# ch559.net
KiCad netlist of a schematic drawn in Altium Designer
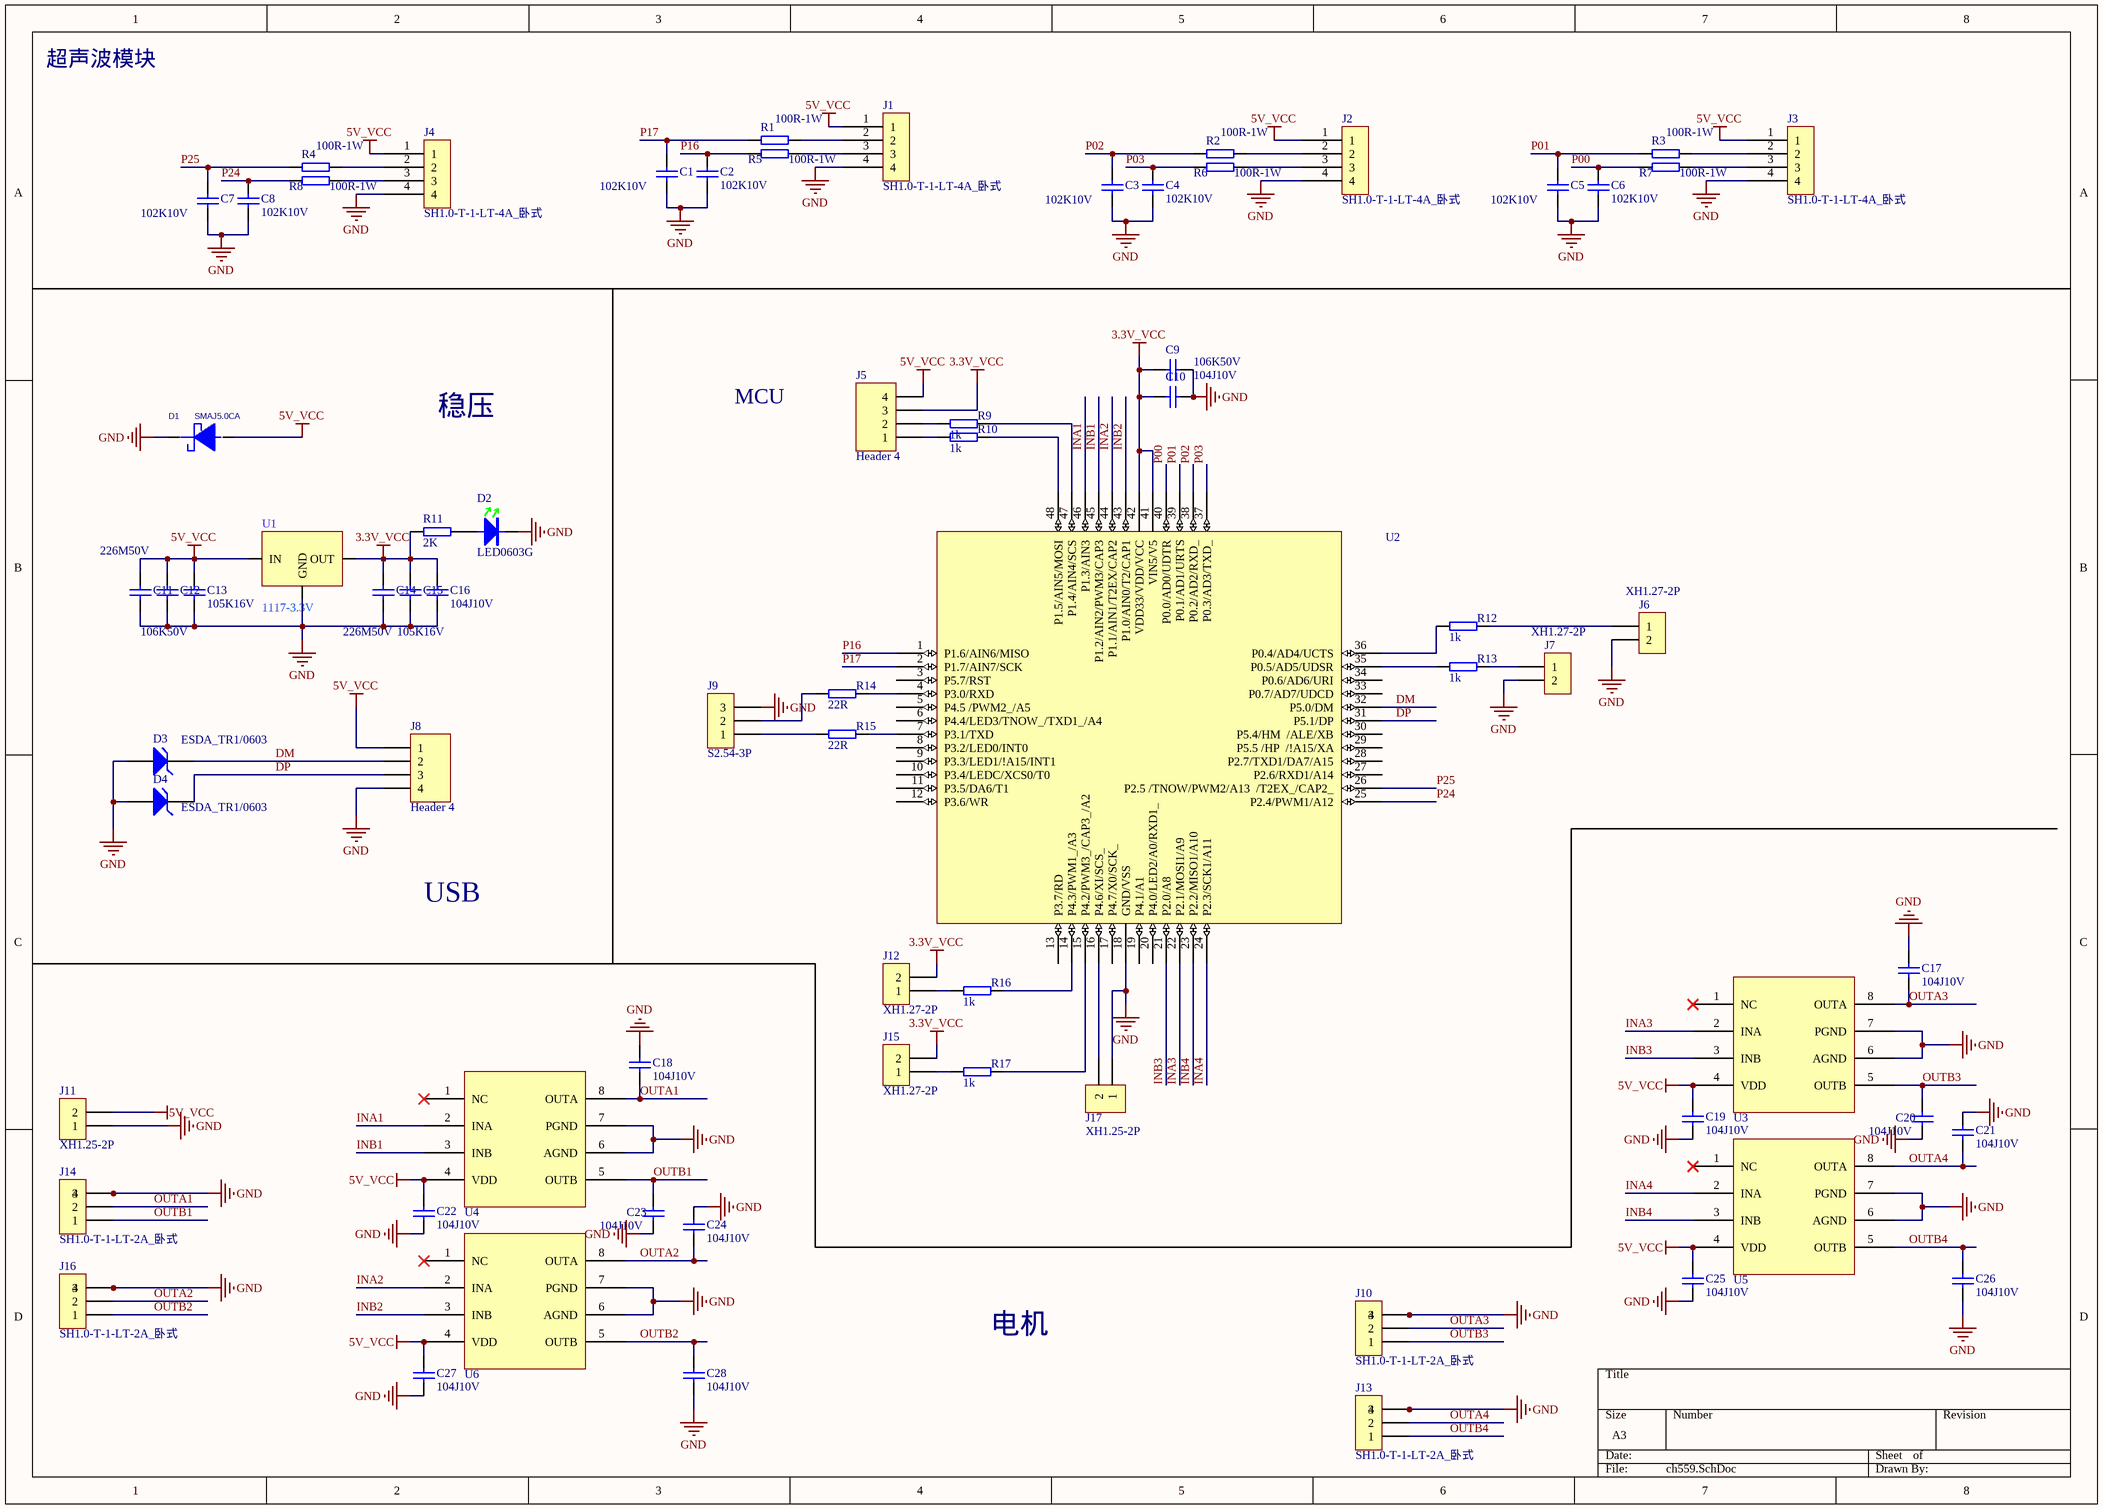
[diagram p0: ch559.SchDoc]

(export (version "E")
  (design (tool "Eeschema 10.0.6"))
  (components
    (comp (ref "C1")
      (value "102K10V")
      (footprint "C0603")
      (description "贴片电容-陶瓷")
      (libsource (lib "Capacitor") (part "C0603X7R-102K10V"))
    )
    (comp (ref "C2")
      (value "102K10V")
      (footprint "C0603")
      (description "贴片电容-陶瓷")
      (libsource (lib "Capacitor") (part "C0603X7R-102K10V"))
    )
    (comp (ref "C3")
      (value "102K10V")
      (footprint "C0603")
      (description "贴片电容-陶瓷")
      (libsource (lib "Capacitor") (part "C0603X7R-102K10V"))
    )
    (comp (ref "C4")
      (value "102K10V")
      (footprint "C0603")
      (description "贴片电容-陶瓷")
      (libsource (lib "Capacitor") (part "C0603X7R-102K10V"))
    )
    (comp (ref "C5")
      (value "102K10V")
      (footprint "C0603")
      (description "贴片电容-陶瓷")
      (libsource (lib "Capacitor") (part "C0603X7R-102K10V"))
    )
    (comp (ref "C6")
      (value "102K10V")
      (footprint "C0603")
      (description "贴片电容-陶瓷")
      (libsource (lib "Capacitor") (part "C0603X7R-102K10V"))
    )
    (comp (ref "C7")
      (value "102K10V")
      (footprint "C0603")
      (description "贴片电容-陶瓷")
      (libsource (lib "Capacitor") (part "C0603X7R-102K10V"))
    )
    (comp (ref "C8")
      (value "102K10V")
      (footprint "C0603")
      (description "贴片电容-陶瓷")
      (libsource (lib "Capacitor") (part "C0603X7R-102K10V"))
    )
    (comp (ref "C9")
      (value "106K50V")
      (footprint "C0603")
      (description "贴片电容-陶瓷")
      (libsource (lib "AIWAC-bolsterV01") (part "C0603X7R-106K50V"))
    )
    (comp (ref "C10")
      (value "104J10V")
      (footprint "C0402")
      (description "贴片电容-陶瓷")
      (libsource (lib "AIWAC-bolsterV01") (part "C0402X7R-104J10V"))
    )
    (comp (ref "C11")
      (value "226M50V")
      (footprint "C0805")
      (description "贴片电容-陶瓷")
      (libsource (lib "AIWAC-bolsterV01") (part "C0805Y5V-226M50V"))
    )
    (comp (ref "C12")
      (value "106K50V")
      (footprint "C0603")
      (description "贴片电容-陶瓷")
      (libsource (lib "AIWAC-bolsterV01") (part "C0603X7R-106K50V"))
    )
    (comp (ref "C13")
      (value "105K16V")
      (footprint "C0603")
      (description "贴片电容-陶瓷")
      (libsource (lib "AIWAC-bolsterV01") (part "C0603X7R-105K16V"))
    )
    (comp (ref "C14")
      (value "226M50V")
      (footprint "C0805")
      (description "贴片电容-陶瓷")
      (libsource (lib "AIWAC-bolsterV01") (part "C0805Y5V-226M50V"))
    )
    (comp (ref "C15")
      (value "105K16V")
      (footprint "C0603")
      (description "贴片电容-陶瓷")
      (libsource (lib "AIWAC-bolsterV01") (part "C0603X7R-105K16V"))
    )
    (comp (ref "C16")
      (value "104J10V")
      (footprint "C0402")
      (description "贴片电容-陶瓷")
      (libsource (lib "AIWAC-bolsterV01") (part "C0402X7R-104J10V"))
    )
    (comp (ref "C17")
      (value "104J10V")
      (footprint "C0402")
      (description "贴片电容-陶瓷")
      (libsource (lib "AIWAC-bolsterV01") (part "C0402X7R-104J10V"))
    )
    (comp (ref "C18")
      (value "104J10V")
      (footprint "C0402")
      (description "贴片电容-陶瓷")
      (libsource (lib "AIWAC-bolsterV01") (part "C0402X7R-104J10V"))
    )
    (comp (ref "C19")
      (value "104J10V")
      (footprint "C0402")
      (description "贴片电容-陶瓷")
      (libsource (lib "AIWAC-bolsterV01") (part "C0402X7R-104J10V"))
    )
    (comp (ref "C20")
      (value "104J10V")
      (footprint "C0402")
      (description "贴片电容-陶瓷")
      (libsource (lib "AIWAC-bolsterV01") (part "C0402X7R-104J10V"))
    )
    (comp (ref "C21")
      (value "104J10V")
      (footprint "C0402")
      (description "贴片电容-陶瓷")
      (libsource (lib "AIWAC-bolsterV01") (part "C0402X7R-104J10V"))
    )
    (comp (ref "C22")
      (value "104J10V")
      (footprint "C0402")
      (description "贴片电容-陶瓷")
      (libsource (lib "AIWAC-bolsterV01") (part "C0402X7R-104J10V"))
    )
    (comp (ref "C23")
      (value "104J10V")
      (footprint "C0402")
      (description "贴片电容-陶瓷")
      (libsource (lib "AIWAC-bolsterV01") (part "C0402X7R-104J10V"))
    )
    (comp (ref "C24")
      (value "104J10V")
      (footprint "C0402")
      (description "贴片电容-陶瓷")
      (libsource (lib "AIWAC-bolsterV01") (part "C0402X7R-104J10V"))
    )
    (comp (ref "C25")
      (value "104J10V")
      (footprint "C0402")
      (description "贴片电容-陶瓷")
      (libsource (lib "AIWAC-bolsterV01") (part "C0402X7R-104J10V"))
    )
    (comp (ref "C26")
      (value "104J10V")
      (footprint "C0402")
      (description "贴片电容-陶瓷")
      (libsource (lib "AIWAC-bolsterV01") (part "C0402X7R-104J10V"))
    )
    (comp (ref "C27")
      (value "104J10V")
      (footprint "C0402")
      (description "贴片电容-陶瓷")
      (libsource (lib "AIWAC-bolsterV01") (part "C0402X7R-104J10V"))
    )
    (comp (ref "C28")
      (value "104J10V")
      (footprint "C0402")
      (description "贴片电容-陶瓷")
      (libsource (lib "AIWAC-bolsterV01") (part "C0402X7R-104J10V"))
    )
    (comp (ref "D1") (value "SMAJ5.0CA") (footprint "DO-214") (libsource (lib "ISO-V3") (part "SMAJ5.0CA")))
    (comp (ref "D2")
      (value "LED0603G")
      (footprint "D-LED0603G")
      (description "贴片二极管-LED")
      (libsource (lib "AIWAC-bolsterV01") (part "DLED-0603-G"))
    )
    (comp (ref "D3")
      (value "ESDA_TR1/0603")
      (footprint "HS_0603D")
      (description "Zener Diode")
      (fields (field (name "PUBLISHER") "*"))
      (libsource (lib "HSC32K1(QFN56)_BlueTooth_V2.0_20171108 - 副本") (part "D Zener"))
    )
    (comp (ref "D4")
      (value "ESDA_TR1/0603")
      (footprint "HS_0603D")
      (description "Zener Diode")
      (fields (field (name "PUBLISHER") "*"))
      (libsource (lib "HSC32K1(QFN56)_BlueTooth_V2.0_20171108 - 副本") (part "D Zener"))
    )
    (comp (ref "J1")
      (value "SH1.0-T-1-LT-4A_卧式")
      (footprint "XH2.54-4P")
      (libsource (lib "Schlib1") (part "SH1.0-T-1-LT-4A_卧式"))
    )
    (comp (ref "J2")
      (value "SH1.0-T-1-LT-4A_卧式")
      (footprint "XH2.54-4P")
      (libsource (lib "Schlib1") (part "SH1.0-T-1-LT-4A_卧式"))
    )
    (comp (ref "J3")
      (value "SH1.0-T-1-LT-4A_卧式")
      (footprint "XH2.54-4P")
      (libsource (lib "Schlib1") (part "SH1.0-T-1-LT-4A_卧式"))
    )
    (comp (ref "J4")
      (value "SH1.0-T-1-LT-4A_卧式")
      (footprint "XH2.54-4P")
      (libsource (lib "Schlib1") (part "SH1.0-T-1-LT-4A_卧式"))
    )
    (comp (ref "J5")
      (value "Header 4")
      (footprint "J-SH1.27 -4")
      (description "Header, 4-Pin")
      (fields (field (name "PUBLISHER") "Altium Limited"))
      (libsource (lib "USB_COM_V1.0") (part "Header 4"))
    )
    (comp (ref "J6")
      (value "XH1.27-2P")
      (footprint "J-SH1.27-2")
      (description "接插件-1.27")
      (libsource (lib "USB_COM_V1.0") (part "J-XH1.27-2P"))
    )
    (comp (ref "J7")
      (value "XH1.27-2P")
      (footprint "J-SH1.27-2")
      (description "接插件-1.27")
      (libsource (lib "USB_COM_V1.0") (part "J-XH1.27-2P"))
    )
    (comp (ref "J8")
      (value "Header 4")
      (footprint "XH2.54-4P")
      (description "Header, 4-Pin")
      (fields (field (name "PUBLISHER") "Altium Limited"))
      (libsource (lib "Miscellaneous Connectors") (part "Header 4"))
    )
    (comp (ref "J9")
      (value "S2.54-3P")
      (footprint "S2.54-3P")
      (description "单排排针-直针")
      (libsource (lib "PCB_Project") (part "J-S2.54-3P"))
    )
    (comp (ref "J10")
      (value "SH1.0-T-1-LT-2A_卧式")
      (footprint "J-SH2.0-T-1-LT-2A_立式")
      (libsource (lib "Connector") (part "SH1.0-T-1-LT-2A_卧式"))
    )
    (comp (ref "J11")
      (value "XH1.25-2P")
      (footprint "XH2.54-2p")
      (description "接插件-2.54")
      (libsource (lib "USB_COM_V1.0") (part "J-XH2.54-2P_1"))
    )
    (comp (ref "J12")
      (value "XH1.27-2P")
      (footprint "J-SH1.27-2")
      (description "接插件-1.27")
      (libsource (lib "") (part "J-XH1.27-2P_1"))
    )
    (comp (ref "J13")
      (value "SH1.0-T-1-LT-2A_卧式")
      (footprint "J-SH2.0-T-1-LT-2A_立式")
      (libsource (lib "Connector") (part "SH1.0-T-1-LT-2A_卧式"))
    )
    (comp (ref "J14")
      (value "SH1.0-T-1-LT-2A_卧式")
      (footprint "J-SH2.0-T-1-LT-2A_立式")
      (libsource (lib "Connector") (part "SH1.0-T-1-LT-2A_卧式"))
    )
    (comp (ref "J15")
      (value "XH1.27-2P")
      (footprint "J-SH1.27-2")
      (description "接插件-1.27")
      (libsource (lib "") (part "J-XH1.27-2P_1"))
    )
    (comp (ref "J16")
      (value "SH1.0-T-1-LT-2A_卧式")
      (footprint "J-SH2.0-T-1-LT-2A_立式")
      (libsource (lib "Connector") (part "SH1.0-T-1-LT-2A_卧式"))
    )
    (comp (ref "J17")
      (value "XH1.25-2P")
      (footprint "S1.25-2P")
      (description "接插件-2.54")
      (libsource (lib "AIWAC-bolsterV01") (part "J-XH2.54-2P"))
    )
    (comp (ref "R1")
      (value "100R-1W")
      (footprint "R0603")
      (description "插件电阻-碳膜")
      (libsource (lib "Resistor") (part "R1-100R"))
    )
    (comp (ref "R2")
      (value "100R-1W")
      (footprint "R0603")
      (description "插件电阻-碳膜")
      (libsource (lib "Resistor") (part "R1-100R"))
    )
    (comp (ref "R3")
      (value "100R-1W")
      (footprint "R0603")
      (description "插件电阻-碳膜")
      (libsource (lib "Resistor") (part "R1-100R"))
    )
    (comp (ref "R4")
      (value "100R-1W")
      (footprint "R0603")
      (description "插件电阻-碳膜")
      (libsource (lib "Resistor") (part "R1-100R"))
    )
    (comp (ref "R5")
      (value "100R-1W")
      (footprint "R0603")
      (description "插件电阻-碳膜")
      (libsource (lib "Resistor") (part "R1-100R"))
    )
    (comp (ref "R6")
      (value "100R-1W")
      (footprint "R0603")
      (description "插件电阻-碳膜")
      (libsource (lib "Resistor") (part "R1-100R"))
    )
    (comp (ref "R7")
      (value "100R-1W")
      (footprint "R0603")
      (description "插件电阻-碳膜")
      (libsource (lib "Resistor") (part "R1-100R"))
    )
    (comp (ref "R8")
      (value "100R-1W")
      (footprint "R0603")
      (description "插件电阻-碳膜")
      (libsource (lib "Resistor") (part "R1-100R"))
    )
    (comp (ref "R9")
      (value "1k")
      (footprint "R0603")
      (description "贴片电阻-通用")
      (libsource (lib "Resistor") (part "R0603-100RF"))
    )
    (comp (ref "R10")
      (value "1k")
      (footprint "R0603")
      (description "贴片电阻-通用")
      (libsource (lib "Resistor") (part "R0603-100RF"))
    )
    (comp (ref "R11")
      (value "2K")
      (footprint "R0603")
      (description "贴片电阻-通用")
      (libsource (lib "Resistor") (part "R0603-100RF"))
    )
    (comp (ref "R12")
      (value "1k")
      (footprint "R0603")
      (description "贴片电阻-通用")
      (libsource (lib "Resistor") (part "R0603-100RF"))
    )
    (comp (ref "R13")
      (value "1k")
      (footprint "R0603")
      (description "贴片电阻-通用")
      (libsource (lib "Resistor") (part "R0603-100RF"))
    )
    (comp (ref "R14")
      (value "22R")
      (footprint "R0603")
      (description "贴片电阻-通用")
      (libsource (lib "Resistor") (part "R0603-100RF"))
    )
    (comp (ref "R15")
      (value "22R")
      (footprint "R0603")
      (description "贴片电阻-通用")
      (libsource (lib "Resistor") (part "R0603-100RF"))
    )
    (comp (ref "R16")
      (value "1k")
      (footprint "R0603")
      (description "贴片电阻-通用")
      (libsource (lib "Resistor") (part "R0603-100RF"))
    )
    (comp (ref "R17")
      (value "1k")
      (footprint "R0603")
      (description "贴片电阻-通用")
      (libsource (lib "Resistor") (part "R0603-100RF"))
    )
    (comp (ref "U1")
      (value "1117-3.3V")
      (footprint "SOT-223")
      (description "芯片 电源类")
      (libsource (lib "标准通用原理图库") (part "AP1117-33 SOT-223"))
    )
    (comp (ref "U2")
      (value "CH559L")
      (footprint "LQFP48")
      (description "单片机")
      (libsource (lib "PCB_Project") (part "CH559L"))
    )
    (comp (ref "U3")
      (value "PTC918")
      (footprint "SO-8")
      (description "马达驱动芯片")
      (libsource (lib "USB_COM_V1.0") (part "PTC918"))
    )
    (comp (ref "U4")
      (value "PTC918")
      (footprint "SO-8")
      (description "马达驱动芯片")
      (libsource (lib "USB_COM_V1.0") (part "PTC918"))
    )
    (comp (ref "U5")
      (value "PTC918")
      (footprint "SO-8")
      (description "马达驱动芯片")
      (libsource (lib "USB_COM_V1.0") (part "PTC918"))
    )
    (comp (ref "U6")
      (value "PTC918")
      (footprint "SO-8")
      (description "马达驱动芯片")
      (libsource (lib "USB_COM_V1.0") (part "PTC918"))
    )
  )
  (nets
    (net (code "1") (name "/DM") (class "Default")
      (node (ref "D3") (pin "2") (pinfunction "K_2") (pintype "passive"))
      (node (ref "J8") (pin "2") (pinfunction "2_2") (pintype "passive"))
      (node (ref "U2") (pin "32") (pinfunction "P5.0/DM_32") (pintype "bidirectional"))
    )
    (net (code "2") (name "/DP") (class "Default")
      (node (ref "D4") (pin "2") (pinfunction "K_2") (pintype "passive"))
      (node (ref "J8") (pin "3") (pinfunction "3_3") (pintype "passive"))
      (node (ref "U2") (pin "31") (pinfunction "P5.1/DP_31") (pintype "bidirectional"))
    )
    (net (code "3") (name "/INA1") (class "Default")
      (node (ref "U2") (pin "46") (pinfunction "P1.3/AIN3_46") (pintype "bidirectional"))
      (node (ref "U4") (pin "2") (pinfunction "INA_2") (pintype "passive"))
    )
    (net (code "4") (name "/INA2") (class "Default")
      (node (ref "U2") (pin "44") (pinfunction "P1.1/AIN1/T2EX/CAP2_44") (pintype "bidirectional"))
      (node (ref "U6") (pin "2") (pinfunction "INA_2") (pintype "passive"))
    )
    (net (code "5") (name "/INA3") (class "Default")
      (node (ref "U2") (pin "22") (pinfunction "P2.1/MOSI1/A9_22") (pintype "bidirectional"))
      (node (ref "U3") (pin "2") (pinfunction "INA_2") (pintype "passive"))
    )
    (net (code "6") (name "/INA4") (class "Default")
      (node (ref "U2") (pin "24") (pinfunction "P2.3/SCK1/A11_24") (pintype "bidirectional"))
      (node (ref "U5") (pin "2") (pinfunction "INA_2") (pintype "passive"))
    )
    (net (code "7") (name "/INB1") (class "Default")
      (node (ref "U2") (pin "45") (pinfunction "P1.2/AIN2/PWM3/CAP3_45") (pintype "bidirectional"))
      (node (ref "U4") (pin "3") (pinfunction "INB_3") (pintype "passive"))
    )
    (net (code "8") (name "/INB2") (class "Default")
      (node (ref "U2") (pin "43") (pinfunction "P1.0/AIN0/T2/CAP1_43") (pintype "bidirectional"))
      (node (ref "U6") (pin "3") (pinfunction "INB_3") (pintype "passive"))
    )
    (net (code "9") (name "/INB3") (class "Default")
      (node (ref "U2") (pin "21") (pinfunction "P2.0/A8_21") (pintype "bidirectional"))
      (node (ref "U3") (pin "3") (pinfunction "INB_3") (pintype "passive"))
    )
    (net (code "10") (name "/INB4") (class "Default")
      (node (ref "U2") (pin "23") (pinfunction "P2.2/MISO1/A10_23") (pintype "bidirectional"))
      (node (ref "U5") (pin "3") (pinfunction "INB_3") (pintype "passive"))
    )
    (net (code "11") (name "/OUTA1") (class "Default")
      (node (ref "C18") (pin "2") (pinfunction "2_2") (pintype "passive"))
      (node (ref "J14") (pin "2") (pinfunction "2_2") (pintype "passive"))
      (node (ref "U4") (pin "8") (pinfunction "OUTA_8") (pintype "passive"))
    )
    (net (code "12") (name "/OUTA2") (class "Default")
      (node (ref "C24") (pin "2") (pinfunction "2_2") (pintype "passive"))
      (node (ref "J16") (pin "2") (pinfunction "2_2") (pintype "passive"))
      (node (ref "U6") (pin "8") (pinfunction "OUTA_8") (pintype "passive"))
    )
    (net (code "13") (name "/OUTA3") (class "Default")
      (node (ref "C17") (pin "2") (pinfunction "2_2") (pintype "passive"))
      (node (ref "J10") (pin "2") (pinfunction "2_2") (pintype "passive"))
      (node (ref "U3") (pin "8") (pinfunction "OUTA_8") (pintype "passive"))
    )
    (net (code "14") (name "/OUTA4") (class "Default")
      (node (ref "C21") (pin "2") (pinfunction "2_2") (pintype "passive"))
      (node (ref "J13") (pin "2") (pinfunction "2_2") (pintype "passive"))
      (node (ref "U5") (pin "8") (pinfunction "OUTA_8") (pintype "passive"))
    )
    (net (code "15") (name "/OUTB1") (class "Default")
      (node (ref "C23") (pin "1") (pinfunction "1_1") (pintype "passive"))
      (node (ref "J14") (pin "1") (pinfunction "1_1") (pintype "passive"))
      (node (ref "U4") (pin "5") (pinfunction "OUTB_5") (pintype "passive"))
    )
    (net (code "16") (name "/OUTB2") (class "Default")
      (node (ref "C28") (pin "1") (pinfunction "1_1") (pintype "passive"))
      (node (ref "J16") (pin "1") (pinfunction "1_1") (pintype "passive"))
      (node (ref "U6") (pin "5") (pinfunction "OUTB_5") (pintype "passive"))
    )
    (net (code "17") (name "/OUTB3") (class "Default")
      (node (ref "C20") (pin "1") (pinfunction "1_1") (pintype "passive"))
      (node (ref "J10") (pin "1") (pinfunction "1_1") (pintype "passive"))
      (node (ref "U3") (pin "5") (pinfunction "OUTB_5") (pintype "passive"))
    )
    (net (code "18") (name "/OUTB4") (class "Default")
      (node (ref "C26") (pin "1") (pinfunction "1_1") (pintype "passive"))
      (node (ref "J13") (pin "1") (pinfunction "1_1") (pintype "passive"))
      (node (ref "U5") (pin "5") (pinfunction "OUTB_5") (pintype "passive"))
    )
    (net (code "19") (name "/P00") (class "Default")
      (node (ref "C6") (pin "1") (pinfunction "1_1") (pintype "passive"))
      (node (ref "R7") (pin "1") (pinfunction "1_1") (pintype "passive"))
      (node (ref "U2") (pin "40") (pinfunction "P0.0/AD0/UDTR_40") (pintype "bidirectional"))
    )
    (net (code "20") (name "/P01") (class "Default")
      (node (ref "C5") (pin "1") (pinfunction "1_1") (pintype "passive"))
      (node (ref "R3") (pin "1") (pinfunction "1_1") (pintype "passive"))
      (node (ref "U2") (pin "39") (pinfunction "P0.1/AD1/URTS_39") (pintype "bidirectional"))
    )
    (net (code "21") (name "/P02") (class "Default")
      (node (ref "C3") (pin "1") (pinfunction "1_1") (pintype "passive"))
      (node (ref "R2") (pin "1") (pinfunction "1_1") (pintype "passive"))
      (node (ref "U2") (pin "38") (pinfunction "P0.2/AD2/RXD__38") (pintype "bidirectional"))
    )
    (net (code "22") (name "/P03") (class "Default")
      (node (ref "C4") (pin "1") (pinfunction "1_1") (pintype "passive"))
      (node (ref "R6") (pin "1") (pinfunction "1_1") (pintype "passive"))
      (node (ref "U2") (pin "37") (pinfunction "P0.3/AD3/TXD__37") (pintype "bidirectional"))
    )
    (net (code "23") (name "/P16") (class "Default")
      (node (ref "C2") (pin "1") (pinfunction "1_1") (pintype "passive"))
      (node (ref "R5") (pin "1") (pinfunction "1_1") (pintype "passive"))
      (node (ref "U2") (pin "1") (pinfunction "P1.6/AIN6/MISO_1") (pintype "bidirectional"))
    )
    (net (code "24") (name "/P17") (class "Default")
      (node (ref "C1") (pin "1") (pinfunction "1_1") (pintype "passive"))
      (node (ref "R1") (pin "1") (pinfunction "1_1") (pintype "passive"))
      (node (ref "U2") (pin "2") (pinfunction "P1.7/AIN7/SCK_2") (pintype "bidirectional"))
    )
    (net (code "25") (name "/P24") (class "Default")
      (node (ref "C8") (pin "1") (pinfunction "1_1") (pintype "passive"))
      (node (ref "R8") (pin "1") (pinfunction "1_1") (pintype "passive"))
      (node (ref "U2") (pin "25") (pinfunction "P2.4/PWM1/A12_25") (pintype "bidirectional"))
    )
    (net (code "26") (name "/P25") (class "Default")
      (node (ref "C7") (pin "1") (pinfunction "1_1") (pintype "passive"))
      (node (ref "R4") (pin "1") (pinfunction "1_1") (pintype "passive"))
      (node (ref "U2") (pin "26") (pinfunction "P2.5_/TNOW/PWM2/A13__/T2EX_/CAP2__26") (pintype "bidirectional"))
    )
    (net (code "27") (name "3.3V_VCC") (class "Default")
      (node (ref "C10") (pin "2") (pinfunction "2_2") (pintype "passive"))
      (node (ref "C14") (pin "1") (pinfunction "1_1") (pintype "passive"))
      (node (ref "C15") (pin "2") (pinfunction "2_2") (pintype "passive"))
      (node (ref "C16") (pin "1") (pinfunction "1_1") (pintype "passive"))
      (node (ref "C9") (pin "2") (pinfunction "2_2") (pintype "passive"))
      (node (ref "J12") (pin "2") (pinfunction "2_2") (pintype "passive"))
      (node (ref "J15") (pin "2") (pinfunction "2_2") (pintype "passive"))
      (node (ref "J5") (pin "3") (pinfunction "3_3") (pintype "passive"))
      (node (ref "R11") (pin "2") (pinfunction "2_2") (pintype "passive"))
      (node (ref "U1") (pin "2") (pinfunction "OUT_2") (pintype "passive"))
      (node (ref "U2") (pin "41") (pinfunction "VIN5/V5_41") (pintype "passive"))
      (node (ref "U2") (pin "42") (pinfunction "VDD33/VDD/VCC_42") (pintype "passive"))
    )
    (net (code "28") (name "5V_VCC") (class "Default")
      (node (ref "C11") (pin "1") (pinfunction "1_1") (pintype "passive"))
      (node (ref "C12") (pin "1") (pinfunction "1_1") (pintype "passive"))
      (node (ref "C13") (pin "1") (pinfunction "1_1") (pintype "passive"))
      (node (ref "C19") (pin "1") (pinfunction "1_1") (pintype "passive"))
      (node (ref "C22") (pin "1") (pinfunction "1_1") (pintype "passive"))
      (node (ref "C25") (pin "1") (pinfunction "1_1") (pintype "passive"))
      (node (ref "C27") (pin "1") (pinfunction "1_1") (pintype "passive"))
      (node (ref "D1") (pin "1") (pinfunction "+_1") (pintype "passive"))
      (node (ref "J1") (pin "1") (pinfunction "1_1") (pintype "passive"))
      (node (ref "J11") (pin "2") (pinfunction "2_2") (pintype "passive"))
      (node (ref "J2") (pin "1") (pinfunction "1_1") (pintype "passive"))
      (node (ref "J3") (pin "1") (pinfunction "1_1") (pintype "passive"))
      (node (ref "J4") (pin "1") (pinfunction "1_1") (pintype "passive"))
      (node (ref "J5") (pin "4") (pinfunction "4_4") (pintype "passive"))
      (node (ref "J8") (pin "1") (pinfunction "1_1") (pintype "passive"))
      (node (ref "U1") (pin "3") (pinfunction "IN_3") (pintype "passive"))
      (node (ref "U3") (pin "4") (pinfunction "VDD_4") (pintype "passive"))
      (node (ref "U4") (pin "4") (pinfunction "VDD_4") (pintype "passive"))
      (node (ref "U5") (pin "4") (pinfunction "VDD_4") (pintype "passive"))
      (node (ref "U6") (pin "4") (pinfunction "VDD_4") (pintype "passive"))
    )
    (net (code "29") (name "GND") (class "Default")
      (node (ref "C1") (pin "2") (pinfunction "2_2") (pintype "passive"))
      (node (ref "C10") (pin "1") (pinfunction "1_1") (pintype "passive"))
      (node (ref "C11") (pin "2") (pinfunction "2_2") (pintype "passive"))
      (node (ref "C12") (pin "2") (pinfunction "2_2") (pintype "passive"))
      (node (ref "C13") (pin "2") (pinfunction "2_2") (pintype "passive"))
      (node (ref "C14") (pin "2") (pinfunction "2_2") (pintype "passive"))
      (node (ref "C15") (pin "1") (pinfunction "1_1") (pintype "passive"))
      (node (ref "C16") (pin "2") (pinfunction "2_2") (pintype "passive"))
      (node (ref "C17") (pin "1") (pinfunction "1_1") (pintype "passive"))
      (node (ref "C18") (pin "1") (pinfunction "1_1") (pintype "passive"))
      (node (ref "C19") (pin "2") (pinfunction "2_2") (pintype "passive"))
      (node (ref "C2") (pin "2") (pinfunction "2_2") (pintype "passive"))
      (node (ref "C20") (pin "2") (pinfunction "2_2") (pintype "passive"))
      (node (ref "C21") (pin "1") (pinfunction "1_1") (pintype "passive"))
      (node (ref "C22") (pin "2") (pinfunction "2_2") (pintype "passive"))
      (node (ref "C23") (pin "2") (pinfunction "2_2") (pintype "passive"))
      (node (ref "C24") (pin "1") (pinfunction "1_1") (pintype "passive"))
      (node (ref "C25") (pin "2") (pinfunction "2_2") (pintype "passive"))
      (node (ref "C26") (pin "2") (pinfunction "2_2") (pintype "passive"))
      (node (ref "C27") (pin "2") (pinfunction "2_2") (pintype "passive"))
      (node (ref "C28") (pin "2") (pinfunction "2_2") (pintype "passive"))
      (node (ref "C3") (pin "2") (pinfunction "2_2") (pintype "passive"))
      (node (ref "C4") (pin "2") (pinfunction "2_2") (pintype "passive"))
      (node (ref "C5") (pin "2") (pinfunction "2_2") (pintype "passive"))
      (node (ref "C6") (pin "2") (pinfunction "2_2") (pintype "passive"))
      (node (ref "C7") (pin "2") (pinfunction "2_2") (pintype "passive"))
      (node (ref "C8") (pin "2") (pinfunction "2_2") (pintype "passive"))
      (node (ref "C9") (pin "1") (pinfunction "1_1") (pintype "passive"))
      (node (ref "D1") (pin "2") (pinfunction "-_2") (pintype "passive"))
      (node (ref "D2") (pin "2") (pinfunction "2_2") (pintype "passive"))
      (node (ref "D3") (pin "1") (pinfunction "A_1") (pintype "passive"))
      (node (ref "D4") (pin "1") (pinfunction "A_1") (pintype "passive"))
      (node (ref "J1") (pin "4") (pinfunction "4_4") (pintype "passive"))
      (node (ref "J10") (pin "3") (pinfunction "3_3") (pintype "passive"))
      (node (ref "J10") (pin "4") (pinfunction "4_4") (pintype "passive"))
      (node (ref "J11") (pin "1") (pinfunction "1_1") (pintype "passive"))
      (node (ref "J13") (pin "3") (pinfunction "3_3") (pintype "passive"))
      (node (ref "J13") (pin "4") (pinfunction "4_4") (pintype "passive"))
      (node (ref "J14") (pin "3") (pinfunction "3_3") (pintype "passive"))
      (node (ref "J14") (pin "4") (pinfunction "4_4") (pintype "passive"))
      (node (ref "J16") (pin "3") (pinfunction "3_3") (pintype "passive"))
      (node (ref "J16") (pin "4") (pinfunction "4_4") (pintype "passive"))
      (node (ref "J17") (pin "1") (pinfunction "1_1") (pintype "passive"))
      (node (ref "J2") (pin "4") (pinfunction "4_4") (pintype "passive"))
      (node (ref "J3") (pin "4") (pinfunction "4_4") (pintype "passive"))
      (node (ref "J4") (pin "4") (pinfunction "4_4") (pintype "passive"))
      (node (ref "J6") (pin "2") (pinfunction "2_2") (pintype "passive"))
      (node (ref "J7") (pin "2") (pinfunction "2_2") (pintype "passive"))
      (node (ref "J8") (pin "4") (pinfunction "4_4") (pintype "passive"))
      (node (ref "J9") (pin "3") (pinfunction "3_3") (pintype "passive"))
      (node (ref "U1") (pin "1") (pinfunction "GND_1") (pintype "passive"))
      (node (ref "U2") (pin "18") (pinfunction "GND/VSS_18") (pintype "passive"))
      (node (ref "U3") (pin "6") (pinfunction "AGND_6") (pintype "passive"))
      (node (ref "U3") (pin "7") (pinfunction "PGND_7") (pintype "passive"))
      (node (ref "U4") (pin "6") (pinfunction "AGND_6") (pintype "passive"))
      (node (ref "U4") (pin "7") (pinfunction "PGND_7") (pintype "passive"))
      (node (ref "U5") (pin "6") (pinfunction "AGND_6") (pintype "passive"))
      (node (ref "U5") (pin "7") (pinfunction "PGND_7") (pintype "passive"))
      (node (ref "U6") (pin "6") (pinfunction "AGND_6") (pintype "passive"))
      (node (ref "U6") (pin "7") (pinfunction "PGND_7") (pintype "passive"))
    )
    (net (code "30") (name "Net-(D2-Pad1)") (class "Default")
      (node (ref "D2") (pin "1") (pinfunction "1_1") (pintype "passive"))
      (node (ref "R11") (pin "1") (pinfunction "1_1") (pintype "passive"))
    )
    (net (code "31") (name "Net-(J1-Pad2)") (class "Default")
      (node (ref "J1") (pin "2") (pinfunction "2_2") (pintype "passive"))
      (node (ref "R1") (pin "2") (pinfunction "2_2") (pintype "passive"))
    )
    (net (code "32") (name "Net-(J1-Pad3)") (class "Default")
      (node (ref "J1") (pin "3") (pinfunction "3_3") (pintype "passive"))
      (node (ref "R5") (pin "2") (pinfunction "2_2") (pintype "passive"))
    )
    (net (code "33") (name "Net-(J2-Pad2)") (class "Default")
      (node (ref "J2") (pin "2") (pinfunction "2_2") (pintype "passive"))
      (node (ref "R2") (pin "2") (pinfunction "2_2") (pintype "passive"))
    )
    (net (code "34") (name "Net-(J2-Pad3)") (class "Default")
      (node (ref "J2") (pin "3") (pinfunction "3_3") (pintype "passive"))
      (node (ref "R6") (pin "2") (pinfunction "2_2") (pintype "passive"))
    )
    (net (code "35") (name "Net-(J3-Pad2)") (class "Default")
      (node (ref "J3") (pin "2") (pinfunction "2_2") (pintype "passive"))
      (node (ref "R3") (pin "2") (pinfunction "2_2") (pintype "passive"))
    )
    (net (code "36") (name "Net-(J3-Pad3)") (class "Default")
      (node (ref "J3") (pin "3") (pinfunction "3_3") (pintype "passive"))
      (node (ref "R7") (pin "2") (pinfunction "2_2") (pintype "passive"))
    )
    (net (code "37") (name "Net-(J4-Pad2)") (class "Default")
      (node (ref "J4") (pin "2") (pinfunction "2_2") (pintype "passive"))
      (node (ref "R4") (pin "2") (pinfunction "2_2") (pintype "passive"))
    )
    (net (code "38") (name "Net-(J4-Pad3)") (class "Default")
      (node (ref "J4") (pin "3") (pinfunction "3_3") (pintype "passive"))
      (node (ref "R8") (pin "2") (pinfunction "2_2") (pintype "passive"))
    )
    (net (code "39") (name "Net-(J5-Pad1)") (class "Default")
      (node (ref "J5") (pin "1") (pinfunction "1_1") (pintype "passive"))
      (node (ref "R10") (pin "1") (pinfunction "1_1") (pintype "passive"))
    )
    (net (code "40") (name "Net-(J5-Pad2)") (class "Default")
      (node (ref "J5") (pin "2") (pinfunction "2_2") (pintype "passive"))
      (node (ref "R9") (pin "1") (pinfunction "1_1") (pintype "passive"))
    )
    (net (code "41") (name "Net-(J6-Pad1)") (class "Default")
      (node (ref "J6") (pin "1") (pinfunction "1_1") (pintype "passive"))
      (node (ref "R12") (pin "2") (pinfunction "2_2") (pintype "passive"))
    )
    (net (code "42") (name "Net-(J7-Pad1)") (class "Default")
      (node (ref "J7") (pin "1") (pinfunction "1_1") (pintype "passive"))
      (node (ref "R13") (pin "2") (pinfunction "2_2") (pintype "passive"))
    )
    (net (code "43") (name "Net-(J9-Pad1)") (class "Default")
      (node (ref "J9") (pin "1") (pinfunction "1_1") (pintype "passive"))
      (node (ref "R15") (pin "1") (pinfunction "1_1") (pintype "passive"))
    )
    (net (code "44") (name "Net-(J9-Pad2)") (class "Default")
      (node (ref "J9") (pin "2") (pinfunction "2_2") (pintype "passive"))
      (node (ref "R14") (pin "1") (pinfunction "1_1") (pintype "passive"))
    )
    (net (code "45") (name "Net-(J12-Pad1)") (class "Default")
      (node (ref "J12") (pin "1") (pinfunction "1_1") (pintype "passive"))
      (node (ref "R16") (pin "1") (pinfunction "1_1") (pintype "passive"))
    )
    (net (code "46") (name "Net-(J15-Pad1)") (class "Default")
      (node (ref "J15") (pin "1") (pinfunction "1_1") (pintype "passive"))
      (node (ref "R17") (pin "1") (pinfunction "1_1") (pintype "passive"))
    )
    (net (code "47") (name "Net-(U2-P0.4{slash}AD4{slash}UCTS)") (class "Default")
      (node (ref "R12") (pin "1") (pinfunction "1_1") (pintype "passive"))
      (node (ref "U2") (pin "36") (pinfunction "P0.4/AD4/UCTS_36") (pintype "bidirectional"))
    )
    (net (code "48") (name "Net-(U2-P0.5{slash}AD5{slash}UDSR)") (class "Default")
      (node (ref "R13") (pin "1") (pinfunction "1_1") (pintype "passive"))
      (node (ref "U2") (pin "35") (pinfunction "P0.5/AD5/UDSR_35") (pintype "bidirectional"))
    )
    (net (code "49") (name "Net-(U2-P1.4{slash}AIN4{slash}SCS)") (class "Default")
      (node (ref "R9") (pin "2") (pinfunction "2_2") (pintype "passive"))
      (node (ref "U2") (pin "47") (pinfunction "P1.4/AIN4/SCS_47") (pintype "bidirectional"))
    )
    (net (code "50") (name "Net-(U2-P1.5{slash}AIN5{slash}MOSI)") (class "Default")
      (node (ref "R10") (pin "2") (pinfunction "2_2") (pintype "passive"))
      (node (ref "U2") (pin "48") (pinfunction "P1.5/AIN5/MOSI_48") (pintype "bidirectional"))
    )
    (net (code "51") (name "Net-(U2-P3.0{slash}RXD)") (class "Default")
      (node (ref "R14") (pin "2") (pinfunction "2_2") (pintype "passive"))
      (node (ref "U2") (pin "4") (pinfunction "P3.0/RXD_4") (pintype "bidirectional"))
    )
    (net (code "52") (name "Net-(U2-P3.1{slash}TXD)") (class "Default")
      (node (ref "R15") (pin "2") (pinfunction "2_2") (pintype "passive"))
      (node (ref "U2") (pin "7") (pinfunction "P3.1/TXD_7") (pintype "bidirectional"))
    )
    (net (code "53") (name "Net-(U2-P4.2{slash}PWM3_{slash}CAP3_{slash}A2)") (class "Default")
      (node (ref "R17") (pin "2") (pinfunction "2_2") (pintype "passive"))
      (node (ref "U2") (pin "15") (pinfunction "P4.2/PWM3_/CAP3_/A2_15") (pintype "bidirectional"))
    )
    (net (code "54") (name "Net-(U2-P4.3{slash}PWM1_{slash}A3)") (class "Default")
      (node (ref "R16") (pin "2") (pinfunction "2_2") (pintype "passive"))
      (node (ref "U2") (pin "14") (pinfunction "P4.3/PWM1_/A3_14") (pintype "bidirectional"))
    )
    (net (code "55") (name "Net-(U2-P4.6{slash}XI{slash}SCS_)") (class "Default")
      (node (ref "J17") (pin "2") (pinfunction "2_2") (pintype "passive"))
      (node (ref "U2") (pin "16") (pinfunction "P4.6/XI/SCS__16") (pintype "bidirectional"))
    )
    (net (code "56") (name "unconnected-(U2-P0.6{slash}AD6{slash}URI-Pad34)") (class "Default")
      (node (ref "U2") (pin "34") (pinfunction "P0.6/AD6/URI_34") (pintype "bidirectional"))
    )
    (net (code "57") (name "unconnected-(U2-P0.7{slash}AD7{slash}UDCD-Pad33)") (class "Default")
      (node (ref "U2") (pin "33") (pinfunction "P0.7/AD7/UDCD_33") (pintype "bidirectional"))
    )
    (net (code "58") (name "unconnected-(U2-P2.6{slash}RXD1{slash}A14-Pad27)") (class "Default")
      (node (ref "U2") (pin "27") (pinfunction "P2.6/RXD1/A14_27") (pintype "bidirectional"))
    )
    (net (code "59") (name "unconnected-(U2-P2.7{slash}TXD1{slash}DA7{slash}A15-Pad28)") (class "Default")
      (node (ref "U2") (pin "28") (pinfunction "P2.7/TXD1/DA7/A15_28") (pintype "bidirectional"))
    )
    (net (code "60") (name "unconnected-(U2-P3.2{slash}LED0{slash}INT0-Pad8)") (class "Default")
      (node (ref "U2") (pin "8") (pinfunction "P3.2/LED0/INT0_8") (pintype "bidirectional"))
    )
    (net (code "61") (name "unconnected-(U2-P3.3{slash}LED1{slash}!A15{slash}INT1-Pad9)") (class "Default")
      (node (ref "U2") (pin "9") (pinfunction "P3.3/LED1/!A15/INT1_9") (pintype "bidirectional"))
    )
    (net (code "62") (name "unconnected-(U2-P3.4{slash}LEDC{slash}XCS0{slash}T0-Pad10)") (class "Default")
      (node (ref "U2") (pin "10") (pinfunction "P3.4/LEDC/XCS0/T0_10") (pintype "bidirectional"))
    )
    (net (code "63") (name "unconnected-(U2-P3.5{slash}DA6{slash}T1-Pad11)") (class "Default")
      (node (ref "U2") (pin "11") (pinfunction "P3.5/DA6/T1_11") (pintype "bidirectional"))
    )
    (net (code "64") (name "unconnected-(U2-P3.6{slash}WR-Pad12)") (class "Default")
      (node (ref "U2") (pin "12") (pinfunction "P3.6/WR_12") (pintype "bidirectional"))
    )
    (net (code "65") (name "unconnected-(U2-P3.7{slash}RD-Pad13)") (class "Default")
      (node (ref "U2") (pin "13") (pinfunction "P3.7/RD_13") (pintype "bidirectional"))
    )
    (net (code "66") (name "unconnected-(U2-P4.0{slash}LED2{slash}A0{slash}RXD1_-Pad20)") (class "Default")
      (node (ref "U2") (pin "20") (pinfunction "P4.0/LED2/A0/RXD1__20") (pintype "bidirectional"))
    )
    (net (code "67") (name "unconnected-(U2-P4.1{slash}A1-Pad19)") (class "Default")
      (node (ref "U2") (pin "19") (pinfunction "P4.1/A1_19") (pintype "bidirectional"))
    )
    (net (code "68") (name "unconnected-(U2-P4.4{slash}LED3{slash}TNOW_{slash}TXD1_{slash}A4-Pad6)") (class "Default")
      (node (ref "U2") (pin "6") (pinfunction "P4.4/LED3/TNOW_/TXD1_/A4_6") (pintype "bidirectional"))
    )
    (net (code "69") (name "unconnected-(U2-P4.5_{slash}PWM2_{slash}A5-Pad5)") (class "Default")
      (node (ref "U2") (pin "5") (pinfunction "P4.5_/PWM2_/A5_5") (pintype "bidirectional"))
    )
    (net (code "70") (name "unconnected-(U2-P4.7{slash}X0{slash}SCK_-Pad17)") (class "Default")
      (node (ref "U2") (pin "17") (pinfunction "P4.7/X0/SCK__17") (pintype "bidirectional"))
    )
    (net (code "71") (name "unconnected-(U2-P5.4{slash}HM__{slash}ALE{slash}XB-Pad30)") (class "Default")
      (node (ref "U2") (pin "30") (pinfunction "P5.4/HM__/ALE/XB_30") (pintype "bidirectional"))
    )
    (net (code "72") (name "unconnected-(U2-P5.5_{slash}HP__{slash}!A15{slash}XA-Pad29)") (class "Default")
      (node (ref "U2") (pin "29") (pinfunction "P5.5_/HP__/!A15/XA_29") (pintype "bidirectional"))
    )
    (net (code "73") (name "unconnected-(U2-P5.7{slash}RST-Pad3)") (class "Default")
      (node (ref "U2") (pin "3") (pinfunction "P5.7/RST_3") (pintype "bidirectional"))
    )
    (net (code "74") (name "unconnected-(U3-NC-Pad1)") (class "Default")
      (node (ref "U3") (pin "1") (pinfunction "NC_1") (pintype "passive+no_connect"))
    )
    (net (code "75") (name "unconnected-(U4-NC-Pad1)") (class "Default")
      (node (ref "U4") (pin "1") (pinfunction "NC_1") (pintype "passive+no_connect"))
    )
    (net (code "76") (name "unconnected-(U5-NC-Pad1)") (class "Default")
      (node (ref "U5") (pin "1") (pinfunction "NC_1") (pintype "passive+no_connect"))
    )
    (net (code "77") (name "unconnected-(U6-NC-Pad1)") (class "Default")
      (node (ref "U6") (pin "1") (pinfunction "NC_1") (pintype "passive+no_connect"))
    )
  )
)
